# LPCB223_-_24V_POWER.net
KiCad netlist of a schematic drawn in Altium Designer
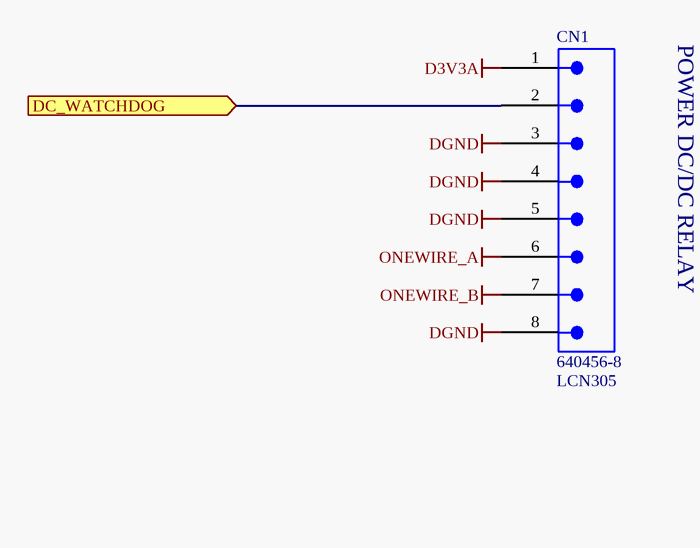
[diagram p0: LPCB223 - 24V POWER.SchDoc]

(export (version "E")
  (design (tool "Eeschema 10.0.6"))
  (components
    (comp (ref "CN1")
      (value "640456-8")
      (footprint "640456-8")
      (description "Connector, Male Header, 8 Way")
      (fields (field (name "LDL_NUMBER") "LCN305"))
      (libsource (lib "LDL_Connectors") (part "640456-8"))
    )
  )
  (nets
    (net (code "1") (name "/DC_WATCHDOG") (class "Default")
      (node (ref "CN1") (pin "2") (pinfunction "2_2") (pintype "passive"))
    )
    (net (code "2") (name "D3V3A") (class "Default")
      (node (ref "CN1") (pin "1") (pinfunction "1_1") (pintype "passive"))
    )
    (net (code "3") (name "DGND") (class "Default")
      (node (ref "CN1") (pin "3") (pinfunction "3_3") (pintype "passive"))
      (node (ref "CN1") (pin "4") (pinfunction "4_4") (pintype "passive"))
      (node (ref "CN1") (pin "5") (pinfunction "5_5") (pintype "passive"))
      (node (ref "CN1") (pin "8") (pinfunction "8_8") (pintype "passive"))
    )
    (net (code "4") (name "ONEWIRE_A") (class "Default")
      (node (ref "CN1") (pin "6") (pinfunction "6_6") (pintype "passive"))
    )
    (net (code "5") (name "ONEWIRE_B") (class "Default")
      (node (ref "CN1") (pin "7") (pinfunction "7_7") (pintype "passive"))
    )
  )
)
